# FanControl_sch.net
KiCad netlist of a schematic drawn in EasyEDA
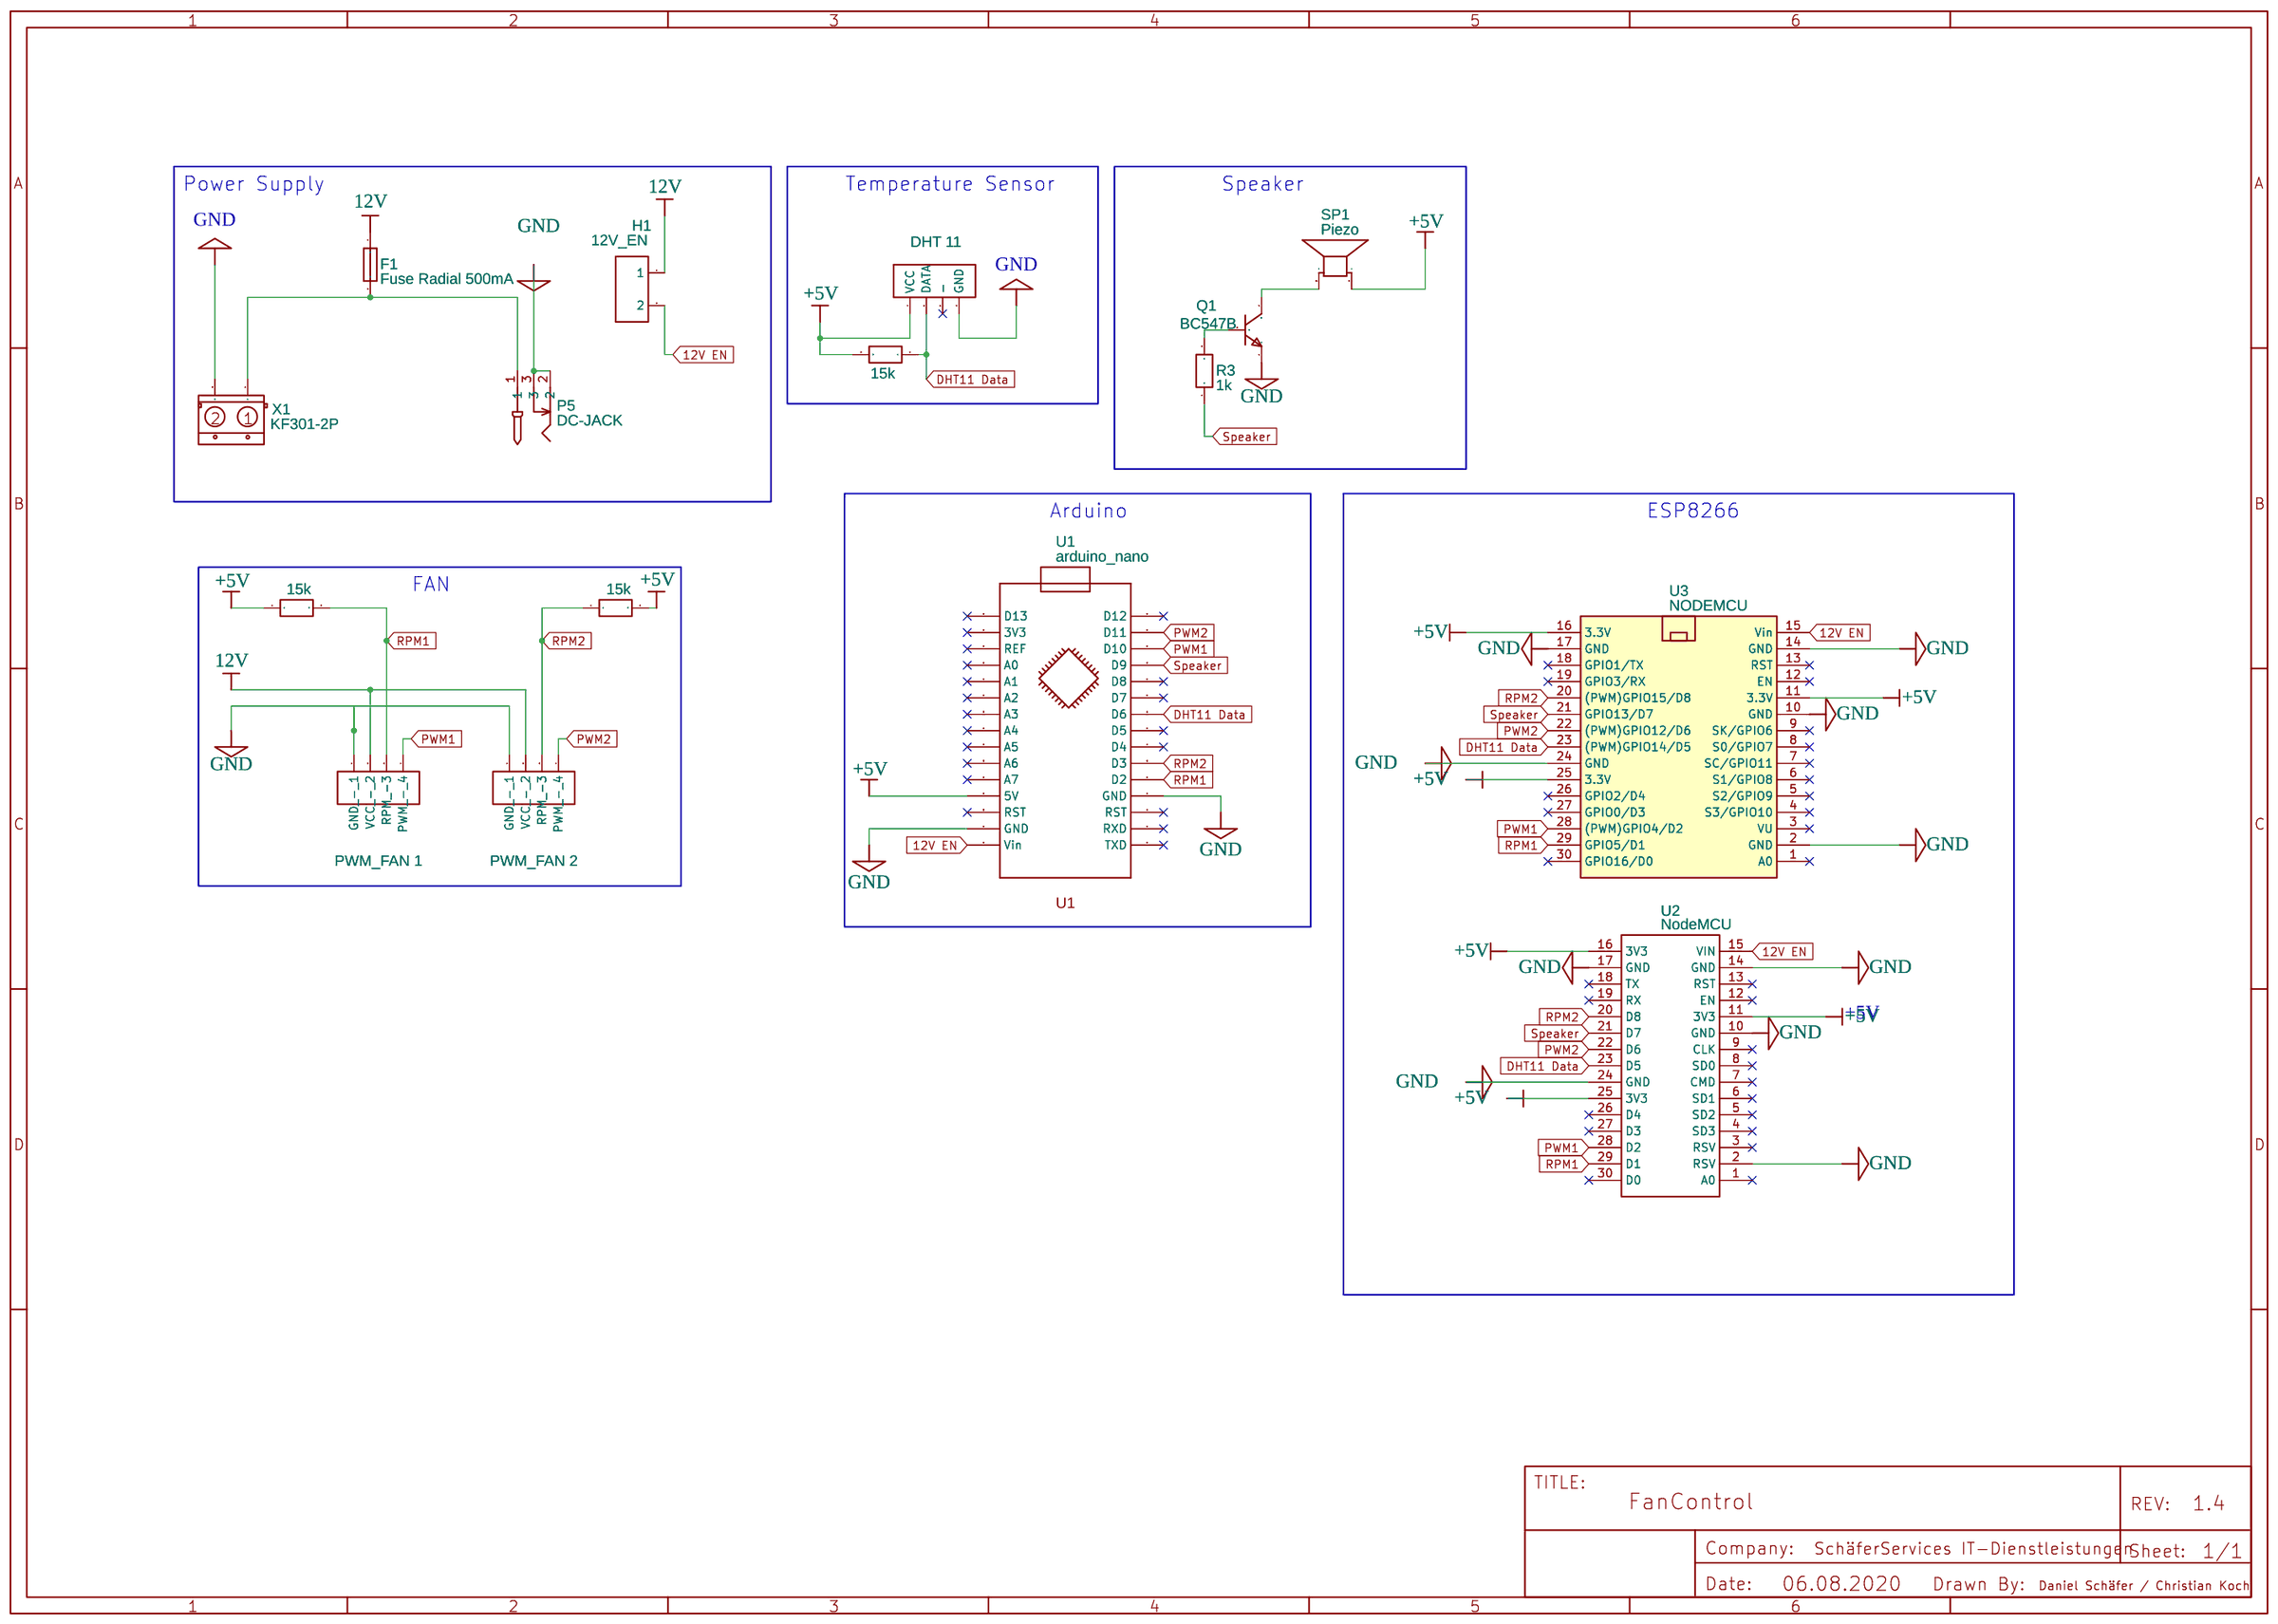
[diagram p0: schematic sheet]

(export (version "E")
  (design (tool "Eeschema 10.0.6"))
  (components
    (comp (ref "F1")
      (value "Fuse Radial 500mA")
      (fields (field (name "BOM_Manufacturer Part") "FUSE RADIAL"))
      (libsource (lib "") (part "Unknown_0_-20"))
    )
    (comp (ref "H1")
      (value "12V_EN")
      (fields (field (name "BOM_Manufacturer Part") "826629-2") (field (name "BOM_Supplier Part") "C86471"))
      (libsource (lib "") (part "Unknown_165_-5"))
    )
    (comp (ref "P1")
      (value "PWM_FAN 1")
      (fields
        (field (name "BOM_Manufacturer Part") "Header-Female-2.54_1x4")
        (field (name "BOM_Supplier Part") "C124413")
      )
      (libsource (lib "") (part "Unknown_5_295"))
    )
    (comp (ref "P2")
      (value "PWM_FAN 2")
      (fields
        (field (name "BOM_Manufacturer Part") "Header-Female-2.54_1x4")
        (field (name "BOM_Supplier Part") "C124413")
      )
      (libsource (lib "") (part "Unknown_100_295"))
    )
    (comp (ref "P3")
      (value "DHT 11")
      (fields
        (field (name "BOM_Manufacturer Part") "Header-Female-2.54_1x4")
        (field (name "BOM_Supplier Part") "C124413")
      )
      (libsource (lib "") (part "Unknown_345_-5"))
    )
    (comp (ref "P5")
      (value "DC-JACK")
      (fields
        (field (name "BOM_Manufacturer Part") "DC005-2.5MM")
        (field (name "BOM_Supplier Part") "E68942")
      )
      (libsource (lib "") (part "Unknown_100_65"))
    )
    (comp (ref "Q1")
      (value "BC547B")
      (fields (field (name "BOM_Manufacturer Part") "BC547B Tube") (field (name "BOM_Supplier Part") "C2092"))
      (libsource (lib "") (part "Unknown_535_20"))
    )
    (comp (ref "R1")
      (value "15k")
      (fields (field (name "BOM_Manufacturer Part") "?"))
      (libsource (lib "") (part "Res_AXIAL-0.3(1/8W)_EU"))
    )
    (comp (ref "R2")
      (value "15k")
      (fields (field (name "BOM_Manufacturer Part") "?"))
      (libsource (lib "") (part "Res_AXIAL-0.3(1/8W)_EU_1"))
    )
    (comp (ref "R3")
      (value "1k")
      (fields (field (name "BOM_Manufacturer Part") "?"))
      (libsource (lib "") (part "Res_AXIAL-0.3(1/8W)_EU_2"))
    )
    (comp (ref "R4")
      (value "15k")
      (fields (field (name "BOM_Manufacturer Part") "?"))
      (libsource (lib "") (part "Res_AXIAL-0.3(1/8W)_EU"))
    )
    (comp (ref "SP1") (value "Piezo") (libsource (lib "") (part "Unknown_590_-25")))
    (comp (ref "U1")
      (value "arduino_nano")
      (fields (field (name "BOM_Manufacturer Part") "arduino_nano1"))
      (libsource (lib "") (part "Unknown_485_195"))
    )
    (comp (ref "U2") (value "NodeMCU") (libsource (lib "") (part "NodeMCU")))
    (comp (ref "U3")
      (value "NODEMCU")
      (fields (field (name "BOM_Manufacturer Part") "NodeMcu V3 LoLin"))
      (libsource (lib "") (part "NODEMCU"))
    )
    (comp (ref "X1") (value "KF301-2P") (libsource (lib "") (part "KF301-2P")))
  )
  (nets
    (net (code "1") (name "+5V") (class "Default")
      (node (ref "P3") (pin "4") (pinfunction "VCC_4") (pintype "input"))
      (node (ref "R1") (pin "2") (pinfunction "2_2") (pintype "unspecified"))
      (node (ref "R2") (pin "2") (pinfunction "2_2") (pintype "unspecified"))
      (node (ref "R4") (pin "1") (pinfunction "1_1") (pintype "unspecified"))
      (node (ref "SP1") (pin "P$2") (pinfunction "-_P$2") (pintype "unspecified"))
      (node (ref "U1") (pin "27") (pinfunction "5V_27") (pintype "unspecified"))
      (node (ref "U2") (pin "11") (pinfunction "3V3_11") (pintype "unspecified"))
      (node (ref "U2") (pin "16") (pinfunction "3V3_16") (pintype "unspecified"))
      (node (ref "U2") (pin "25") (pinfunction "3V3_25") (pintype "unspecified"))
      (node (ref "U3") (pin "11") (pinfunction "3.3V_11") (pintype "unspecified"))
      (node (ref "U3") (pin "16") (pinfunction "3.3V_16") (pintype "unspecified"))
      (node (ref "U3") (pin "25") (pinfunction "3.3V_25") (pintype "unspecified"))
    )
    (net (code "2") (name "12V") (class "Default")
      (node (ref "F1") (pin "1") (pinfunction "1_1") (pintype "unspecified"))
      (node (ref "H1") (pin "1") (pinfunction "1_1") (pintype "unspecified"))
      (node (ref "P1") (pin "2") (pinfunction "VCC_-_2_2") (pintype "input"))
      (node (ref "P2") (pin "2") (pinfunction "VCC_-_2_2") (pintype "input"))
    )
    (net (code "3") (name "12V EN") (class "Default")
      (node (ref "H1") (pin "2") (pinfunction "2_2") (pintype "unspecified"))
      (node (ref "U1") (pin "30") (pinfunction "Vin_30") (pintype "unspecified"))
      (node (ref "U2") (pin "15") (pinfunction "VIN_15") (pintype "unspecified"))
      (node (ref "U3") (pin "15") (pinfunction "Vin_15") (pintype "unspecified"))
    )
    (net (code "4") (name "DHT11 Data") (class "Default")
      (node (ref "P3") (pin "3") (pinfunction "DATA_3") (pintype "input"))
      (node (ref "R2") (pin "1") (pinfunction "1_1") (pintype "unspecified"))
      (node (ref "U1") (pin "9") (pinfunction "D6_9") (pintype "unspecified"))
      (node (ref "U2") (pin "23") (pinfunction "D5_23") (pintype "unspecified"))
      (node (ref "U3") (pin "23") (pinfunction "(PWM)GPIO14/D5_23") (pintype "unspecified"))
    )
    (net (code "5") (name "GND") (class "Default")
      (node (ref "P1") (pin "1") (pinfunction "GND_-_1_1") (pintype "input"))
      (node (ref "P2") (pin "1") (pinfunction "GND_-_1_1") (pintype "input"))
      (node (ref "P3") (pin "1") (pinfunction "GND_1") (pintype "input"))
      (node (ref "P5") (pin "2") (pinfunction "2_2") (pintype "unspecified"))
      (node (ref "P5") (pin "3") (pinfunction "3_3") (pintype "unspecified"))
      (node (ref "Q1") (pin "3") (pinfunction "E_3") (pintype "unspecified"))
      (node (ref "U1") (pin "29") (pinfunction "GND_29") (pintype "unspecified"))
      (node (ref "U1") (pin "4") (pinfunction "GND_4") (pintype "unspecified"))
      (node (ref "U2") (pin "10") (pinfunction "GND_10") (pintype "unspecified"))
      (node (ref "U2") (pin "14") (pinfunction "GND_14") (pintype "unspecified"))
      (node (ref "U2") (pin "17") (pinfunction "GND_17") (pintype "unspecified"))
      (node (ref "U2") (pin "2") (pinfunction "RSV_2") (pintype "unspecified"))
      (node (ref "U2") (pin "24") (pinfunction "GND_24") (pintype "unspecified"))
      (node (ref "U3") (pin "10") (pinfunction "GND_10") (pintype "unspecified"))
      (node (ref "U3") (pin "14") (pinfunction "GND_14") (pintype "unspecified"))
      (node (ref "U3") (pin "17") (pinfunction "GND_17") (pintype "unspecified"))
      (node (ref "U3") (pin "2") (pinfunction "GND_2") (pintype "unspecified"))
      (node (ref "U3") (pin "24") (pinfunction "GND_24") (pintype "unspecified"))
      (node (ref "X1") (pin "2") (pinfunction "2_2") (pintype "unspecified"))
    )
    (net (code "6") (name "Net-(F1-Pad2)") (class "Default")
      (node (ref "F1") (pin "2") (pinfunction "2_2") (pintype "unspecified"))
      (node (ref "P5") (pin "1") (pinfunction "1_1") (pintype "unspecified"))
      (node (ref "X1") (pin "1") (pinfunction "1_1") (pintype "unspecified"))
    )
    (net (code "7") (name "Net-(Q1-B)") (class "Default")
      (node (ref "Q1") (pin "2") (pinfunction "B_2") (pintype "unspecified"))
      (node (ref "R3") (pin "2") (pinfunction "2_2") (pintype "unspecified"))
    )
    (net (code "8") (name "Net-(Q1-C)") (class "Default")
      (node (ref "Q1") (pin "1") (pinfunction "C_1") (pintype "unspecified"))
      (node (ref "SP1") (pin "P$1") (pinfunction "+_P$1") (pintype "unspecified"))
    )
    (net (code "9") (name "PWM1") (class "Default")
      (node (ref "P1") (pin "4") (pinfunction "PWM_-_4_4") (pintype "input"))
      (node (ref "U1") (pin "13") (pinfunction "D10_13") (pintype "unspecified"))
      (node (ref "U2") (pin "28") (pinfunction "D2_28") (pintype "unspecified"))
      (node (ref "U3") (pin "28") (pinfunction "(PWM)GPIO4/D2_28") (pintype "unspecified"))
    )
    (net (code "10") (name "PWM2") (class "Default")
      (node (ref "P2") (pin "4") (pinfunction "PWM_-_4_4") (pintype "input"))
      (node (ref "U1") (pin "14") (pinfunction "D11_14") (pintype "unspecified"))
      (node (ref "U2") (pin "22") (pinfunction "D6_22") (pintype "unspecified"))
      (node (ref "U3") (pin "22") (pinfunction "(PWM)GPIO12/D6_22") (pintype "unspecified"))
    )
    (net (code "11") (name "RPM1") (class "Default")
      (node (ref "P1") (pin "3") (pinfunction "RPM_-3_3") (pintype "input"))
      (node (ref "R4") (pin "2") (pinfunction "2_2") (pintype "unspecified"))
      (node (ref "U1") (pin "5") (pinfunction "D2_5") (pintype "unspecified"))
      (node (ref "U2") (pin "29") (pinfunction "D1_29") (pintype "unspecified"))
      (node (ref "U3") (pin "29") (pinfunction "GPIO5/D1_29") (pintype "unspecified"))
    )
    (net (code "12") (name "RPM2") (class "Default")
      (node (ref "P2") (pin "3") (pinfunction "RPM_-3_3") (pintype "input"))
      (node (ref "R1") (pin "1") (pinfunction "1_1") (pintype "unspecified"))
      (node (ref "U1") (pin "6") (pinfunction "D3_6") (pintype "unspecified"))
      (node (ref "U2") (pin "20") (pinfunction "D8_20") (pintype "unspecified"))
      (node (ref "U3") (pin "20") (pinfunction "(PWM)GPIO15/D8_20") (pintype "unspecified"))
    )
    (net (code "13") (name "Speaker") (class "Default")
      (node (ref "R3") (pin "1") (pinfunction "1_1") (pintype "unspecified"))
      (node (ref "U1") (pin "12") (pinfunction "D9_12") (pintype "unspecified"))
      (node (ref "U2") (pin "21") (pinfunction "D7_21") (pintype "unspecified"))
      (node (ref "U3") (pin "21") (pinfunction "GPIO13/D7_21") (pintype "unspecified"))
    )
    (net (code "14") (name "unconnected-(P3---Pad2)") (class "Default")
      (node (ref "P3") (pin "2") (pinfunction "-_2") (pintype "input+no_connect"))
    )
    (net (code "15") (name "unconnected-(U1-3V3-Pad17)") (class "Default")
      (node (ref "U1") (pin "17") (pinfunction "3V3_17") (pintype "unspecified+no_connect"))
    )
    (net (code "16") (name "unconnected-(U1-A0-Pad19)") (class "Default")
      (node (ref "U1") (pin "19") (pinfunction "A0_19") (pintype "unspecified+no_connect"))
    )
    (net (code "17") (name "unconnected-(U1-A1-Pad20)") (class "Default")
      (node (ref "U1") (pin "20") (pinfunction "A1_20") (pintype "unspecified+no_connect"))
    )
    (net (code "18") (name "unconnected-(U1-A2-Pad21)") (class "Default")
      (node (ref "U1") (pin "21") (pinfunction "A2_21") (pintype "unspecified+no_connect"))
    )
    (net (code "19") (name "unconnected-(U1-A3-Pad22)") (class "Default")
      (node (ref "U1") (pin "22") (pinfunction "A3_22") (pintype "unspecified+no_connect"))
    )
    (net (code "20") (name "unconnected-(U1-A4-Pad23)") (class "Default")
      (node (ref "U1") (pin "23") (pinfunction "A4_23") (pintype "unspecified+no_connect"))
    )
    (net (code "21") (name "unconnected-(U1-A5-Pad24)") (class "Default")
      (node (ref "U1") (pin "24") (pinfunction "A5_24") (pintype "unspecified+no_connect"))
    )
    (net (code "22") (name "unconnected-(U1-A6-Pad25)") (class "Default")
      (node (ref "U1") (pin "25") (pinfunction "A6_25") (pintype "unspecified+no_connect"))
    )
    (net (code "23") (name "unconnected-(U1-A7-Pad26)") (class "Default")
      (node (ref "U1") (pin "26") (pinfunction "A7_26") (pintype "unspecified+no_connect"))
    )
    (net (code "24") (name "unconnected-(U1-D4-Pad7)") (class "Default")
      (node (ref "U1") (pin "7") (pinfunction "D4_7") (pintype "unspecified+no_connect"))
    )
    (net (code "25") (name "unconnected-(U1-D5-Pad8)") (class "Default")
      (node (ref "U1") (pin "8") (pinfunction "D5_8") (pintype "unspecified+no_connect"))
    )
    (net (code "26") (name "unconnected-(U1-D7-Pad10)") (class "Default")
      (node (ref "U1") (pin "10") (pinfunction "D7_10") (pintype "unspecified+no_connect"))
    )
    (net (code "27") (name "unconnected-(U1-D8-Pad11)") (class "Default")
      (node (ref "U1") (pin "11") (pinfunction "D8_11") (pintype "unspecified+no_connect"))
    )
    (net (code "28") (name "unconnected-(U1-D12-Pad15)") (class "Default")
      (node (ref "U1") (pin "15") (pinfunction "D12_15") (pintype "unspecified+no_connect"))
    )
    (net (code "29") (name "unconnected-(U1-D13-Pad16)") (class "Default")
      (node (ref "U1") (pin "16") (pinfunction "D13_16") (pintype "unspecified+no_connect"))
    )
    (net (code "30") (name "unconnected-(U1-REF-Pad18)") (class "Default")
      (node (ref "U1") (pin "18") (pinfunction "REF_18") (pintype "unspecified+no_connect"))
    )
    (net (code "31") (name "unconnected-(U1-RST-Pad3)") (class "Default")
      (node (ref "U1") (pin "3") (pinfunction "RST_3") (pintype "unspecified+no_connect"))
    )
    (net (code "32") (name "unconnected-(U1-RST-Pad28)") (class "Default")
      (node (ref "U1") (pin "28") (pinfunction "RST_28") (pintype "unspecified+no_connect"))
    )
    (net (code "33") (name "unconnected-(U1-RXD-Pad2)") (class "Default")
      (node (ref "U1") (pin "2") (pinfunction "RXD_2") (pintype "unspecified+no_connect"))
    )
    (net (code "34") (name "unconnected-(U1-TXD-Pad1)") (class "Default")
      (node (ref "U1") (pin "1") (pinfunction "TXD_1") (pintype "unspecified+no_connect"))
    )
    (net (code "35") (name "unconnected-(U2-A0-Pad1)") (class "Default")
      (node (ref "U2") (pin "1") (pinfunction "A0_1") (pintype "unspecified+no_connect"))
    )
    (net (code "36") (name "unconnected-(U2-CLK-Pad9)") (class "Default")
      (node (ref "U2") (pin "9") (pinfunction "CLK_9") (pintype "unspecified+no_connect"))
    )
    (net (code "37") (name "unconnected-(U2-CMD-Pad7)") (class "Default")
      (node (ref "U2") (pin "7") (pinfunction "CMD_7") (pintype "unspecified+no_connect"))
    )
    (net (code "38") (name "unconnected-(U2-D0-Pad30)") (class "Default")
      (node (ref "U2") (pin "30") (pinfunction "D0_30") (pintype "unspecified+no_connect"))
    )
    (net (code "39") (name "unconnected-(U2-D3-Pad27)") (class "Default")
      (node (ref "U2") (pin "27") (pinfunction "D3_27") (pintype "unspecified+no_connect"))
    )
    (net (code "40") (name "unconnected-(U2-D4-Pad26)") (class "Default")
      (node (ref "U2") (pin "26") (pinfunction "D4_26") (pintype "unspecified+no_connect"))
    )
    (net (code "41") (name "unconnected-(U2-EN-Pad12)") (class "Default")
      (node (ref "U2") (pin "12") (pinfunction "EN_12") (pintype "unspecified+no_connect"))
    )
    (net (code "42") (name "unconnected-(U2-RST-Pad13)") (class "Default")
      (node (ref "U2") (pin "13") (pinfunction "RST_13") (pintype "unspecified+no_connect"))
    )
    (net (code "43") (name "unconnected-(U2-RSV-Pad3)") (class "Default")
      (node (ref "U2") (pin "3") (pinfunction "RSV_3") (pintype "unspecified+no_connect"))
    )
    (net (code "44") (name "unconnected-(U2-RX-Pad19)") (class "Default")
      (node (ref "U2") (pin "19") (pinfunction "RX_19") (pintype "unspecified+no_connect"))
    )
    (net (code "45") (name "unconnected-(U2-SD0-Pad8)") (class "Default")
      (node (ref "U2") (pin "8") (pinfunction "SD0_8") (pintype "unspecified+no_connect"))
    )
    (net (code "46") (name "unconnected-(U2-SD1-Pad6)") (class "Default")
      (node (ref "U2") (pin "6") (pinfunction "SD1_6") (pintype "unspecified+no_connect"))
    )
    (net (code "47") (name "unconnected-(U2-SD2-Pad5)") (class "Default")
      (node (ref "U2") (pin "5") (pinfunction "SD2_5") (pintype "unspecified+no_connect"))
    )
    (net (code "48") (name "unconnected-(U2-SD3-Pad4)") (class "Default")
      (node (ref "U2") (pin "4") (pinfunction "SD3_4") (pintype "unspecified+no_connect"))
    )
    (net (code "49") (name "unconnected-(U2-TX-Pad18)") (class "Default")
      (node (ref "U2") (pin "18") (pinfunction "TX_18") (pintype "unspecified+no_connect"))
    )
    (net (code "50") (name "unconnected-(U3-A0-Pad1)") (class "Default")
      (node (ref "U3") (pin "1") (pinfunction "A0_1") (pintype "unspecified+no_connect"))
    )
    (net (code "51") (name "unconnected-(U3-EN-Pad12)") (class "Default")
      (node (ref "U3") (pin "12") (pinfunction "EN_12") (pintype "unspecified+no_connect"))
    )
    (net (code "52") (name "unconnected-(U3-GPIO0{slash}D3-Pad27)") (class "Default")
      (node (ref "U3") (pin "27") (pinfunction "GPIO0/D3_27") (pintype "unspecified+no_connect"))
    )
    (net (code "53") (name "unconnected-(U3-GPIO1{slash}TX-Pad18)") (class "Default")
      (node (ref "U3") (pin "18") (pinfunction "GPIO1/TX_18") (pintype "unspecified+no_connect"))
    )
    (net (code "54") (name "unconnected-(U3-GPIO2{slash}D4-Pad26)") (class "Default")
      (node (ref "U3") (pin "26") (pinfunction "GPIO2/D4_26") (pintype "unspecified+no_connect"))
    )
    (net (code "55") (name "unconnected-(U3-GPIO3{slash}RX-Pad19)") (class "Default")
      (node (ref "U3") (pin "19") (pinfunction "GPIO3/RX_19") (pintype "unspecified+no_connect"))
    )
    (net (code "56") (name "unconnected-(U3-GPIO16{slash}D0-Pad30)") (class "Default")
      (node (ref "U3") (pin "30") (pinfunction "GPIO16/D0_30") (pintype "unspecified+no_connect"))
    )
    (net (code "57") (name "unconnected-(U3-RST-Pad13)") (class "Default")
      (node (ref "U3") (pin "13") (pinfunction "RST_13") (pintype "unspecified+no_connect"))
    )
    (net (code "58") (name "unconnected-(U3-S0{slash}GPIO7-Pad8)") (class "Default")
      (node (ref "U3") (pin "8") (pinfunction "S0/GPIO7_8") (pintype "unspecified+no_connect"))
    )
    (net (code "59") (name "unconnected-(U3-S1{slash}GPIO8-Pad6)") (class "Default")
      (node (ref "U3") (pin "6") (pinfunction "S1/GPIO8_6") (pintype "unspecified+no_connect"))
    )
    (net (code "60") (name "unconnected-(U3-S2{slash}GPIO9-Pad5)") (class "Default")
      (node (ref "U3") (pin "5") (pinfunction "S2/GPIO9_5") (pintype "unspecified+no_connect"))
    )
    (net (code "61") (name "unconnected-(U3-S3{slash}GPIO10-Pad4)") (class "Default")
      (node (ref "U3") (pin "4") (pinfunction "S3/GPIO10_4") (pintype "unspecified+no_connect"))
    )
    (net (code "62") (name "unconnected-(U3-SC{slash}GPIO11-Pad7)") (class "Default")
      (node (ref "U3") (pin "7") (pinfunction "SC/GPIO11_7") (pintype "unspecified+no_connect"))
    )
    (net (code "63") (name "unconnected-(U3-SK{slash}GPIO6-Pad9)") (class "Default")
      (node (ref "U3") (pin "9") (pinfunction "SK/GPIO6_9") (pintype "unspecified+no_connect"))
    )
    (net (code "64") (name "unconnected-(U3-VU-Pad3)") (class "Default")
      (node (ref "U3") (pin "3") (pinfunction "VU_3") (pintype "unspecified+no_connect"))
    )
  )
)
